# Interface.net
KiCad netlist of a schematic drawn in Altium Designer
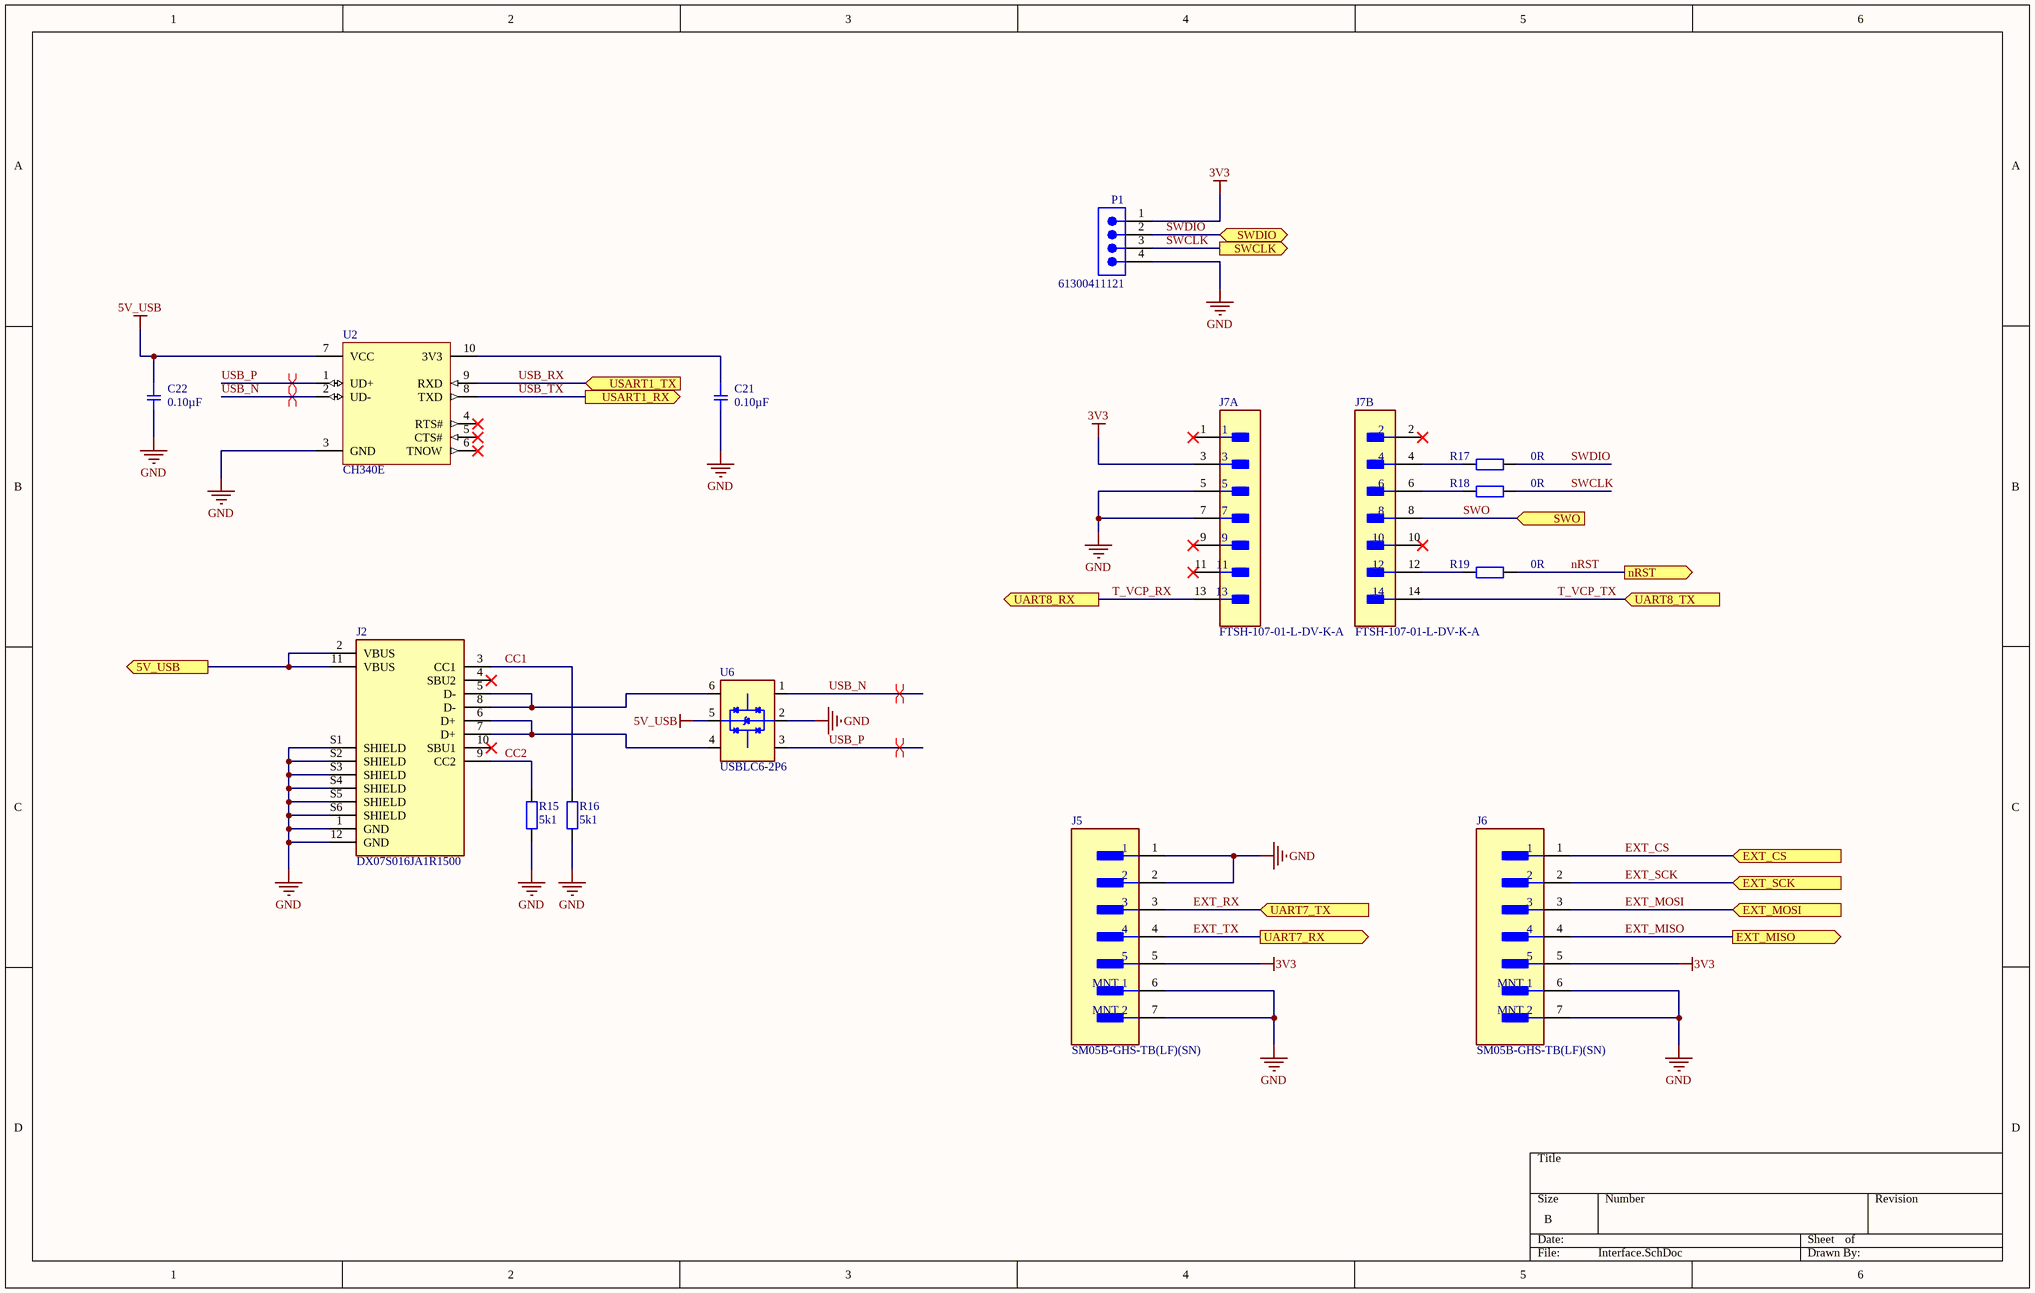
[diagram p0: Interface.SchDoc]

(export (version "E")
  (design (tool "Eeschema 10.0.6"))
  (components
    (comp (ref "C21")
      (value "0.10µF")
      (footprint "SMD-0402C")
      (description "CAP CER 0.1UF 10V X5R 0402")
      (fields (field (name "DIGI-KEY PART NUMBER") "490-6297-1-ND") (field (name "VOLTAGE") "10V"))
      (libsource (lib "University of British Columbia") (part "ZRB15XR61A475ME01D"))
    )
    (comp (ref "C22")
      (value "0.10µF")
      (footprint "SMD-0402C")
      (description "CAP CER 0.1UF 10V X5R 0402")
      (fields (field (name "DIGI-KEY PART NUMBER") "490-6297-1-ND") (field (name "VOLTAGE") "10V"))
      (libsource (lib "University of British Columbia") (part "ZRB15XR61A475ME01D"))
    )
    (comp (ref "J2")
      (value "DX07S016JA1R1500")
      (footprint "JAE_DX07S016JA1R1500")
      (libsource (lib "University of British Columbia") (part "DX07S016JA1R1500"))
    )
    (comp (ref "J5")
      (value "SM05B-GHS-TB(LF)(SN)")
      (footprint "FP-SM05B-GHS-TB_LF_SN-MFG")
      (description "CONN HEADER SMD R/A 5POS 1.25MM")
      (libsource (lib "Altium Content Vault") (part "8ab9848ea90b119fa28a5ddc5abf419"))
    )
    (comp (ref "J6")
      (value "SM05B-GHS-TB(LF)(SN)")
      (footprint "FP-SM05B-GHS-TB_LF_SN-MFG")
      (description "CONN HEADER SMD R/A 5POS 1.25MM")
      (libsource (lib "Altium Content Vault") (part "8ab9848ea90b119fa28a5ddc5abf419"))
    )
    (comp (ref "J7")
      (value "FTSH-107-01-L-DV-K-A")
      (footprint "FP-FTSH-107-01-L-DV-K-A-MFG")
      (description "CONN HEADER SMD 14POS 1.27MM")
      (libsource (lib "Altium Content Vault") (part "45cc164b9edde9e1ad516d884ad4e1e"))
    )
    (comp (ref "P1")
      (value "61300411121")
      (footprint "61300411121")
      (description "THT Vertical Pin Header WR-PHD, Pitch 2.54 mm, Single Row, 4 pins")
      (libsource (lib "Altium Content Vault") (part "Header_Male_1R_04P"))
    )
    (comp (ref "R15")
      (value "5k1")
      (footprint "IPC C R0402 NO SILK")
      (fields (field (name "Comment") "5.1k"))
      (libsource (lib "Jack Kelly") (part "Generic RES 0603"))
    )
    (comp (ref "R16")
      (value "5k1")
      (footprint "IPC C R0402 NO SILK")
      (fields (field (name "Comment") "5.1k"))
      (libsource (lib "Jack Kelly") (part "Generic RES 0603"))
    )
    (comp (ref "R17")
      (value "0R")
      (footprint "IPC C R0402 NO SILK")
      (libsource (lib "Jack Kelly") (part "Generic RES 0603"))
    )
    (comp (ref "R18")
      (value "0R")
      (footprint "IPC C R0402 NO SILK")
      (libsource (lib "Jack Kelly") (part "Generic RES 0603"))
    )
    (comp (ref "R19")
      (value "0R")
      (footprint "IPC C R0402 NO SILK")
      (libsource (lib "Jack Kelly") (part "Generic RES 0603"))
    )
    (comp (ref "U2")
      (value "CH340E")
      (footprint "MSOP-UN10_L")
      (libsource (lib "Jack Kelly") (part "CH340E"))
    )
    (comp (ref "U6")
      (value "USBLC6-2P6")
      (footprint "SOT50P160X60-6N")
      (description "17V Clamp 5A (8/20Âµs) Ipp Tvs Diode Surface Mount SOT-666")
      (fields (field (name "MF") "STMicroelectronics"))
      (libsource (lib "Jack Kelly") (part "USBLC6-2P6"))
    )
  )
  (nets
    (net (code "1") (name "/CC1") (class "Default")
      (node (ref "J2") (pin "3") (pinfunction "CC1_3") (pintype "passive"))
      (node (ref "R16") (pin "1") (pinfunction "1_1") (pintype "passive"))
    )
    (net (code "2") (name "/CC2") (class "Default")
      (node (ref "J2") (pin "9") (pinfunction "CC2_9") (pintype "passive"))
      (node (ref "R15") (pin "1") (pinfunction "1_1") (pintype "passive"))
    )
    (net (code "3") (name "/EXT_CS") (class "Default")
      (node (ref "J6") (pin "1") (pinfunction "1_1") (pintype "passive"))
    )
    (net (code "4") (name "/EXT_MISO") (class "Default")
      (node (ref "J6") (pin "4") (pinfunction "4_4") (pintype "passive"))
    )
    (net (code "5") (name "/EXT_MOSI") (class "Default")
      (node (ref "J6") (pin "3") (pinfunction "3_3") (pintype "passive"))
    )
    (net (code "6") (name "/EXT_RX") (class "Default")
      (node (ref "J5") (pin "3") (pinfunction "3_3") (pintype "passive"))
    )
    (net (code "7") (name "/EXT_SCK") (class "Default")
      (node (ref "J6") (pin "2") (pinfunction "2_2") (pintype "passive"))
    )
    (net (code "8") (name "/EXT_TX") (class "Default")
      (node (ref "J5") (pin "4") (pinfunction "4_4") (pintype "passive"))
    )
    (net (code "9") (name "/SWCLK") (class "Default")
      (node (ref "P1") (pin "3") (pinfunction "3_3") (pintype "passive"))
      (node (ref "R18") (pin "2") (pinfunction "2_2") (pintype "passive"))
    )
    (net (code "10") (name "/SWDIO") (class "Default")
      (node (ref "P1") (pin "2") (pinfunction "2_2") (pintype "passive"))
      (node (ref "R17") (pin "2") (pinfunction "2_2") (pintype "passive"))
    )
    (net (code "11") (name "/SWO") (class "Default")
      (node (ref "J7") (pin "8") (pinfunction "8_8") (pintype "passive"))
    )
    (net (code "12") (name "/T_VCP_RX") (class "Default")
      (node (ref "J7") (pin "13") (pinfunction "13_13") (pintype "passive"))
    )
    (net (code "13") (name "/T_VCP_TX") (class "Default")
      (node (ref "J7") (pin "14") (pinfunction "14_14") (pintype "passive"))
    )
    (net (code "14") (name "/USB_N") (class "Default")
      (node (ref "U2") (pin "2") (pinfunction "UD-_2") (pintype "bidirectional"))
      (node (ref "U6") (pin "1") (pinfunction "I/O1_1_1") (pintype "bidirectional"))
    )
    (net (code "15") (name "/USB_P") (class "Default")
      (node (ref "U2") (pin "1") (pinfunction "UD+_1") (pintype "bidirectional"))
      (node (ref "U6") (pin "3") (pinfunction "I/O2_1_3") (pintype "bidirectional"))
    )
    (net (code "16") (name "/USB_RX") (class "Default")
      (node (ref "U2") (pin "9") (pinfunction "RXD_9") (pintype "input"))
    )
    (net (code "17") (name "/USB_TX") (class "Default")
      (node (ref "U2") (pin "8") (pinfunction "TXD_8") (pintype "output"))
    )
    (net (code "18") (name "/nRST") (class "Default")
      (node (ref "R19") (pin "2") (pinfunction "2_2") (pintype "passive"))
    )
    (net (code "19") (name "3V3") (class "Default")
      (node (ref "J5") (pin "5") (pinfunction "5_5") (pintype "passive"))
      (node (ref "J6") (pin "5") (pinfunction "5_5") (pintype "passive"))
      (node (ref "J7") (pin "3") (pinfunction "3_3") (pintype "passive"))
      (node (ref "P1") (pin "1") (pinfunction "1_1") (pintype "passive"))
    )
    (net (code "20") (name "5V_USB") (class "Default")
      (node (ref "C22") (pin "1") (pinfunction "1_1") (pintype "passive"))
      (node (ref "J2") (pin "11") (pinfunction "VBUS_11") (pintype "power_in"))
      (node (ref "J2") (pin "2") (pinfunction "VBUS_2") (pintype "power_in"))
      (node (ref "U2") (pin "7") (pinfunction "VCC_7") (pintype "power_in"))
      (node (ref "U6") (pin "5") (pinfunction "VBUS_5") (pintype "power_in"))
    )
    (net (code "21") (name "GND") (class "Default")
      (node (ref "C21") (pin "2") (pinfunction "2_2") (pintype "passive"))
      (node (ref "C22") (pin "2") (pinfunction "2_2") (pintype "passive"))
      (node (ref "J2") (pin "1") (pinfunction "GND_1") (pintype "power_in"))
      (node (ref "J2") (pin "12") (pinfunction "GND_12") (pintype "power_in"))
      (node (ref "J2") (pin "S1") (pinfunction "SHIELD_S1") (pintype "passive"))
      (node (ref "J2") (pin "S2") (pinfunction "SHIELD_S2") (pintype "passive"))
      (node (ref "J2") (pin "S3") (pinfunction "SHIELD_S3") (pintype "passive"))
      (node (ref "J2") (pin "S4") (pinfunction "SHIELD_S4") (pintype "passive"))
      (node (ref "J2") (pin "S5") (pinfunction "SHIELD_S5") (pintype "passive"))
      (node (ref "J2") (pin "S6") (pinfunction "SHIELD_S6") (pintype "passive"))
      (node (ref "J5") (pin "1") (pinfunction "1_1") (pintype "passive"))
      (node (ref "J5") (pin "2") (pinfunction "2_2") (pintype "passive"))
      (node (ref "J5") (pin "6") (pinfunction "MNT_1_6") (pintype "passive"))
      (node (ref "J5") (pin "7") (pinfunction "MNT_2_7") (pintype "passive"))
      (node (ref "J6") (pin "6") (pinfunction "MNT_1_6") (pintype "passive"))
      (node (ref "J6") (pin "7") (pinfunction "MNT_2_7") (pintype "passive"))
      (node (ref "J7") (pin "5") (pinfunction "5_5") (pintype "passive"))
      (node (ref "J7") (pin "7") (pinfunction "7_7") (pintype "passive"))
      (node (ref "P1") (pin "4") (pinfunction "4_4") (pintype "passive"))
      (node (ref "R15") (pin "2") (pinfunction "2_2") (pintype "passive"))
      (node (ref "R16") (pin "2") (pinfunction "2_2") (pintype "passive"))
      (node (ref "U2") (pin "3") (pinfunction "GND_3") (pintype "power_in"))
      (node (ref "U6") (pin "2") (pinfunction "GND_2") (pintype "power_in"))
    )
    (net (code "22") (name "Net-(J7-Pad4)") (class "Default")
      (node (ref "J7") (pin "4") (pinfunction "4_4") (pintype "passive"))
      (node (ref "R17") (pin "1") (pinfunction "1_1") (pintype "passive"))
    )
    (net (code "23") (name "Net-(J7-Pad6)") (class "Default")
      (node (ref "J7") (pin "6") (pinfunction "6_6") (pintype "passive"))
      (node (ref "R18") (pin "1") (pinfunction "1_1") (pintype "passive"))
    )
    (net (code "24") (name "Net-(J7-Pad12)") (class "Default")
      (node (ref "J7") (pin "12") (pinfunction "12_12") (pintype "passive"))
      (node (ref "R19") (pin "1") (pinfunction "1_1") (pintype "passive"))
    )
    (net (code "25") (name "Net-(U2-3V3)") (class "Default")
      (node (ref "C21") (pin "1") (pinfunction "1_1") (pintype "passive"))
      (node (ref "U2") (pin "10") (pinfunction "3V3_10") (pintype "power_in"))
    )
    (net (code "26") (name "Net-(U6-I{slash}O1_2)") (class "Default")
      (node (ref "J2") (pin "5") (pinfunction "D-_5") (pintype "passive"))
      (node (ref "J2") (pin "8") (pinfunction "D-_8") (pintype "passive"))
      (node (ref "U6") (pin "6") (pinfunction "I/O1_2_6") (pintype "bidirectional"))
    )
    (net (code "27") (name "Net-(U6-I{slash}O2_2)") (class "Default")
      (node (ref "J2") (pin "6") (pinfunction "D+_6") (pintype "passive"))
      (node (ref "J2") (pin "7") (pinfunction "D+_7") (pintype "passive"))
      (node (ref "U6") (pin "4") (pinfunction "I/O2_2_4") (pintype "bidirectional"))
    )
    (net (code "28") (name "unconnected-(J2-SBU1-Pad10)") (class "Default")
      (node (ref "J2") (pin "10") (pinfunction "SBU1_10") (pintype "passive+no_connect"))
    )
    (net (code "29") (name "unconnected-(J2-SBU2-Pad4)") (class "Default")
      (node (ref "J2") (pin "4") (pinfunction "SBU2_4") (pintype "passive+no_connect"))
    )
    (net (code "30") (name "unconnected-(J7-Pad1)") (class "Default")
      (node (ref "J7") (pin "1") (pinfunction "1_1") (pintype "passive+no_connect"))
    )
    (net (code "31") (name "unconnected-(J7-Pad2)") (class "Default")
      (node (ref "J7") (pin "2") (pinfunction "2_2") (pintype "passive+no_connect"))
    )
    (net (code "32") (name "unconnected-(J7-Pad9)") (class "Default")
      (node (ref "J7") (pin "9") (pinfunction "9_9") (pintype "passive+no_connect"))
    )
    (net (code "33") (name "unconnected-(J7-Pad10)") (class "Default")
      (node (ref "J7") (pin "10") (pinfunction "10_10") (pintype "passive+no_connect"))
    )
    (net (code "34") (name "unconnected-(J7-Pad11)") (class "Default")
      (node (ref "J7") (pin "11") (pinfunction "11_11") (pintype "passive+no_connect"))
    )
    (net (code "35") (name "unconnected-(U2-CTS#-Pad5)") (class "Default")
      (node (ref "U2") (pin "5") (pinfunction "CTS#_5") (pintype "input+no_connect"))
    )
    (net (code "36") (name "unconnected-(U2-RTS#-Pad4)") (class "Default")
      (node (ref "U2") (pin "4") (pinfunction "RTS#_4") (pintype "output+no_connect"))
    )
    (net (code "37") (name "unconnected-(U2-TNOW-Pad6)") (class "Default")
      (node (ref "U2") (pin "6") (pinfunction "TNOW_6") (pintype "output+no_connect"))
    )
  )
)
